# MBP_Universal_Upgrade.net
KiCad netlist of a schematic drawn in Altium Designer
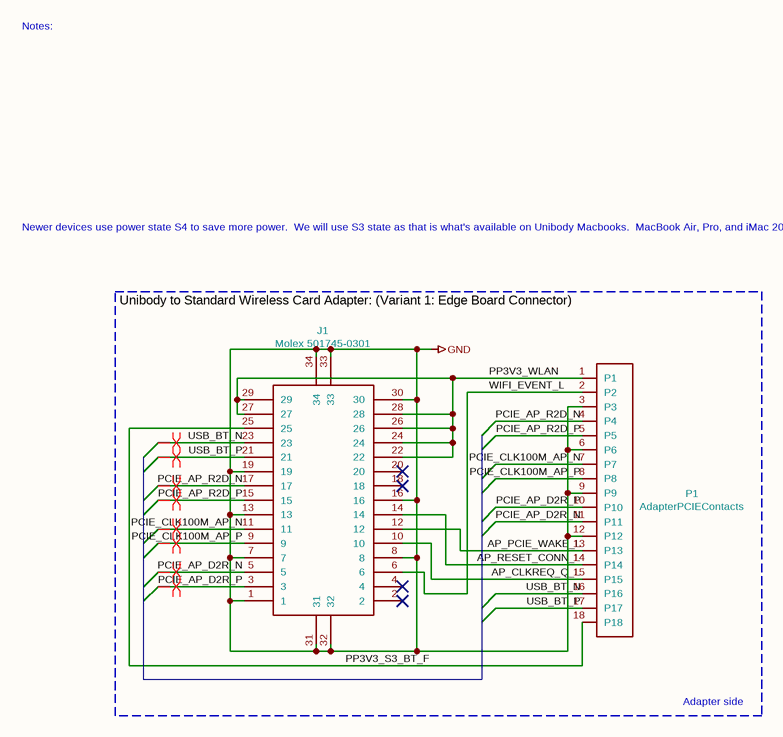
[diagram p0: MBP Universal Upgrade.SchDoc]

(export (version "E")
  (design (tool "Eeschema 10.0.6"))
  (components
    (comp (ref "J1")
      (value "Molex 501745-0301")
      (footprint "5017450301")
      (fields
        (field (name "MOUSER PART NUMBER") "538-501745-0301")
        (field (name "MANUFACTURER_PART_NUMBER") "501745-0301")
      )
      (libsource (lib "SamacSys_Parts") (part "501745-0301"))
    )
    (comp (ref "P1")
      (value "AdapterPCIEContacts")
      (footprint "Edge Connector")
      (libsource (lib "MBPWirelessParts") (part "AdapterPCIEContacts"))
    )
  )
  (nets
    (net (code "1") (name "/AP_CLKREQ_Q_L") (class "Default")
      (node (ref "J1") (pin "10") (pinfunction "10_10") (pintype "passive"))
      (node (ref "P1") (pin "15") (pinfunction "P15_15") (pintype "passive"))
    )
    (net (code "2") (name "/AP_PCIE_WAKE_L") (class "Default")
      (node (ref "J1") (pin "12") (pinfunction "12_12") (pintype "passive"))
      (node (ref "P1") (pin "13") (pinfunction "P13_13") (pintype "passive"))
    )
    (net (code "3") (name "/AP_RESET_CONN_L") (class "Default")
      (node (ref "J1") (pin "14") (pinfunction "14_14") (pintype "passive"))
      (node (ref "P1") (pin "14") (pinfunction "P14_14") (pintype "passive"))
    )
    (net (code "4") (name "/PCIE_AP_D2R_N") (class "Default")
      (node (ref "J1") (pin "5") (pinfunction "5_5") (pintype "passive"))
      (node (ref "P1") (pin "11") (pinfunction "P11_11") (pintype "passive"))
    )
    (net (code "5") (name "/PCIE_AP_D2R_P") (class "Default")
      (node (ref "J1") (pin "3") (pinfunction "3_3") (pintype "passive"))
      (node (ref "P1") (pin "10") (pinfunction "P10_10") (pintype "passive"))
    )
    (net (code "6") (name "/PCIE_AP_R2D_N") (class "Default")
      (node (ref "J1") (pin "17") (pinfunction "17_17") (pintype "passive"))
      (node (ref "P1") (pin "4") (pinfunction "P4_4") (pintype "passive"))
    )
    (net (code "7") (name "/PCIE_AP_R2D_P") (class "Default")
      (node (ref "J1") (pin "15") (pinfunction "15_15") (pintype "passive"))
      (node (ref "P1") (pin "5") (pinfunction "P5_5") (pintype "passive"))
    )
    (net (code "8") (name "/PCIE_CLK100M_AP_N") (class "Default")
      (node (ref "J1") (pin "11") (pinfunction "11_11") (pintype "passive"))
      (node (ref "P1") (pin "7") (pinfunction "P7_7") (pintype "passive"))
    )
    (net (code "9") (name "/PCIE_CLK100M_AP_P") (class "Default")
      (node (ref "J1") (pin "9") (pinfunction "9_9") (pintype "passive"))
      (node (ref "P1") (pin "8") (pinfunction "P8_8") (pintype "passive"))
    )
    (net (code "10") (name "/PP3V3_S3_BT_F") (class "Default")
      (node (ref "J1") (pin "25") (pinfunction "25_25") (pintype "passive"))
      (node (ref "P1") (pin "18") (pinfunction "P18_18") (pintype "passive"))
    )
    (net (code "11") (name "/PP3V3_WLAN") (class "Default")
      (node (ref "J1") (pin "22") (pinfunction "22_22") (pintype "passive"))
      (node (ref "J1") (pin "24") (pinfunction "24_24") (pintype "passive"))
      (node (ref "J1") (pin "26") (pinfunction "26_26") (pintype "passive"))
      (node (ref "J1") (pin "27") (pinfunction "27_27") (pintype "passive"))
      (node (ref "J1") (pin "28") (pinfunction "28_28") (pintype "passive"))
      (node (ref "J1") (pin "29") (pinfunction "29_29") (pintype "passive"))
      (node (ref "P1") (pin "1") (pinfunction "P1_1") (pintype "passive"))
    )
    (net (code "12") (name "/USB_BT_N") (class "Default")
      (node (ref "J1") (pin "23") (pinfunction "23_23") (pintype "passive"))
      (node (ref "P1") (pin "16") (pinfunction "P16_16") (pintype "passive"))
    )
    (net (code "13") (name "/USB_BT_P") (class "Default")
      (node (ref "J1") (pin "21") (pinfunction "21_21") (pintype "passive"))
      (node (ref "P1") (pin "17") (pinfunction "P17_17") (pintype "passive"))
    )
    (net (code "14") (name "/WIFI_EVENT_L") (class "Default")
      (node (ref "J1") (pin "6") (pinfunction "6_6") (pintype "passive"))
      (node (ref "P1") (pin "2") (pinfunction "P2_2") (pintype "passive"))
    )
    (net (code "15") (name "GND") (class "Default")
      (node (ref "J1") (pin "1") (pinfunction "1_1") (pintype "passive"))
      (node (ref "J1") (pin "13") (pinfunction "13_13") (pintype "passive"))
      (node (ref "J1") (pin "16") (pinfunction "16_16") (pintype "passive"))
      (node (ref "J1") (pin "19") (pinfunction "19_19") (pintype "passive"))
      (node (ref "J1") (pin "30") (pinfunction "30_30") (pintype "passive"))
      (node (ref "J1") (pin "31") (pinfunction "31_31") (pintype "passive"))
      (node (ref "J1") (pin "32") (pinfunction "32_32") (pintype "passive"))
      (node (ref "J1") (pin "33") (pinfunction "33_33") (pintype "passive"))
      (node (ref "J1") (pin "34") (pinfunction "34_34") (pintype "passive"))
      (node (ref "J1") (pin "7") (pinfunction "7_7") (pintype "passive"))
      (node (ref "J1") (pin "8") (pinfunction "8_8") (pintype "passive"))
      (node (ref "P1") (pin "12") (pinfunction "P12_12") (pintype "passive"))
      (node (ref "P1") (pin "3") (pinfunction "P3_3") (pintype "passive"))
      (node (ref "P1") (pin "6") (pinfunction "P6_6") (pintype "passive"))
      (node (ref "P1") (pin "9") (pinfunction "P9_9") (pintype "passive"))
    )
    (net (code "16") (name "unconnected-(J1-Pad2)") (class "Default")
      (node (ref "J1") (pin "2") (pinfunction "2_2") (pintype "passive+no_connect"))
    )
    (net (code "17") (name "unconnected-(J1-Pad4)") (class "Default")
      (node (ref "J1") (pin "4") (pinfunction "4_4") (pintype "passive+no_connect"))
    )
    (net (code "18") (name "unconnected-(J1-Pad18)") (class "Default")
      (node (ref "J1") (pin "18") (pinfunction "18_18") (pintype "passive+no_connect"))
    )
    (net (code "19") (name "unconnected-(J1-Pad20)") (class "Default")
      (node (ref "J1") (pin "20") (pinfunction "20_20") (pintype "passive+no_connect"))
    )
  )
)
